# FLASH_MEMORY.net
KiCad netlist of a schematic drawn in Altium Designer
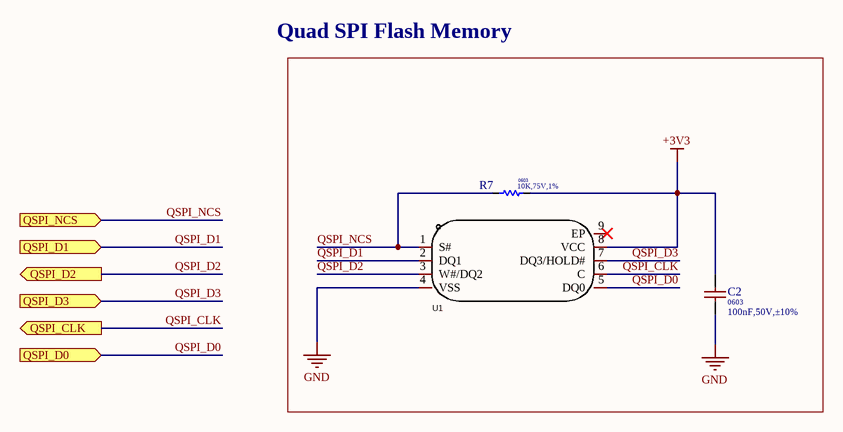
[diagram p0: FLASH MEMORY.SchDoc]

(export (version "E")
  (design (tool "Eeschema 10.0.6"))
  (components
    (comp (ref "C2")
      (value "100nF,50V,±10%")
      (footprint "RCL:C0603")
      (description "50V 100nF X7R ±10% 0603 Multilayer Ceramic Capacitors MLCC - SMD/SMT ROHS")
      (fields
        (field (name "MPN") "CL10B104KB8NNNC")
        (field (name "MANUFACTURER") "SAMSUNG")
        (field (name "PACKAGE") "0603")
      )
      (libsource (lib "RCL") (part "CL10B104KB8NNNC"))
    )
    (comp (ref "R7")
      (value "10K,75V,1%")
      (footprint "R0603")
      (description "100mW Thick Film Resistors ±100ppm/℃ ±1% 10kΩ 0603 Chip Resistor - Surface Mount ROHS")
      (fields
        (field (name "MPN") "0603WAF1002T5E")
        (field (name "MANUFACTURER") "UNI-ROYAL(Uniroyal Elec)")
        (field (name "PACKAGE") "0603")
      )
      (libsource (lib "RCL") (part "0603WAF1002T5E"))
    )
    (comp (ref "U1")
      (value "MT25QL128ABA1EW9-0SIT")
      (footprint "WSON-8(6x8)")
      (description "WSON-8(6x8) NOR FLASH ROHS")
      (fields (field (name "MANUFACTURER") "micron(镁光)"))
      (libsource (lib "IC") (part "MT25QL128ABA1EW9-0SIT"))
    )
  )
  (nets
    (net (code "1") (name "+3V3") (class "Default")
      (node (ref "C2") (pin "2") (pinfunction "2_2") (pintype "passive"))
      (node (ref "R7") (pin "2") (pinfunction "2_2") (pintype "passive"))
      (node (ref "U1") (pin "8") (pinfunction "VCC_8") (pintype "passive"))
    )
    (net (code "2") (name "/QSPI_CLK") (class "Default")
      (node (ref "U1") (pin "6") (pinfunction "C_6") (pintype "passive"))
    )
    (net (code "3") (name "/QSPI_D0") (class "Default")
      (node (ref "U1") (pin "5") (pinfunction "DQ0_5") (pintype "passive"))
    )
    (net (code "4") (name "/QSPI_D1") (class "Default")
      (node (ref "U1") (pin "2") (pinfunction "DQ1_2") (pintype "passive"))
    )
    (net (code "5") (name "/QSPI_D2") (class "Default")
      (node (ref "U1") (pin "3") (pinfunction "W#/DQ2_3") (pintype "passive"))
    )
    (net (code "6") (name "/QSPI_D3") (class "Default")
      (node (ref "U1") (pin "7") (pinfunction "DQ3/HOLD#_7") (pintype "passive"))
    )
    (net (code "7") (name "/QSPI_NCS") (class "Default")
      (node (ref "R7") (pin "1") (pinfunction "1_1") (pintype "passive"))
      (node (ref "U1") (pin "1") (pinfunction "S#_1") (pintype "passive"))
    )
    (net (code "8") (name "GND") (class "Default")
      (node (ref "C2") (pin "1") (pinfunction "1_1") (pintype "passive"))
      (node (ref "U1") (pin "4") (pinfunction "VSS_4") (pintype "passive"))
    )
    (net (code "9") (name "unconnected-(U1-EP-Pad9)") (class "Default")
      (node (ref "U1") (pin "9") (pinfunction "EP_9") (pintype "passive+no_connect"))
    )
  )
)
